# PSU3.net
KiCad netlist of a schematic drawn in Altium Designer
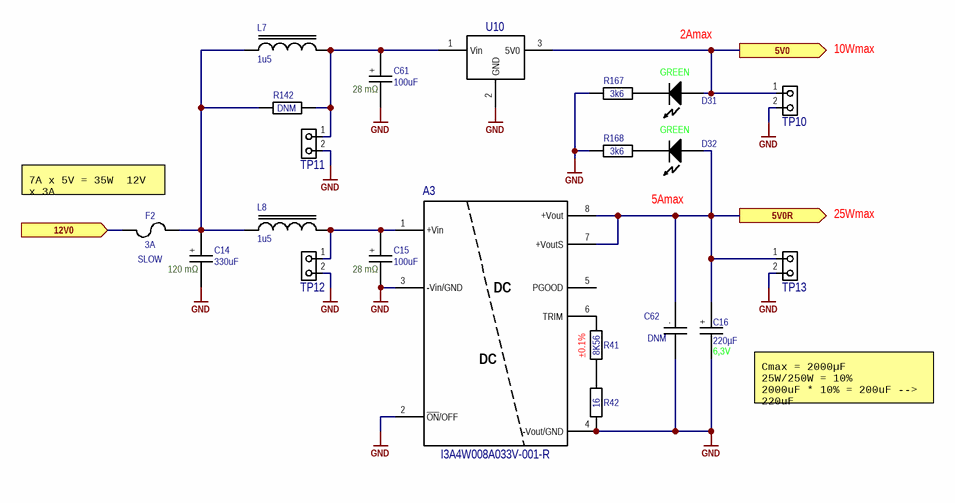
[diagram p0: PSU3.SchDoc]

(export (version "E")
  (design (tool "Eeschema 10.0.6"))
  (components
    (comp (ref "A3")
      (value "A")
      (footprint "I3A-POSETIVE")
      (description "DC DC CONVERTER 3.3-16.5V")
      (fields
        (field (name "02. DISTRIBUTOR PART NUMBER") "285-2720-ND")
        (field (name "07. MANUFACTURER  PART NUMBER") "I3A4W008A033V-001-R")
        (field (name "NICNAME") "I3A4W008A033V-001-R")
        (field (name "13. CREATED DATE/NAME") "AUG 2018 / Hören")
      )
      (libsource (lib "tom") (part "i3A4W008A033V-001-R"))
    )
    (comp (ref "C14")
      (value "330uF")
      (footprint "SMD-CAP-ALU-G")
      (description "CAP ALUM 330UF 20% 50V SMD")
      (fields
        (field (name "TOLERANCE") "±20%")
        (field (name "ESR") "120 mΩ")
        (field (name "02. DISTRIBUTOR PART NUMBER") "PCE5026DKR-ND")
        (field (name "13. CREATED DATE/NAME") "AUG2018/Hören")
      )
      (libsource (lib "chickenfood") (part "C+"))
    )
    (comp (ref "C15")
      (value "100uF")
      (footprint "SMD-CAP-ALU-G")
      (description "CAP ALUM POLY HYB 100UF 50V SMD")
      (fields
        (field (name "TOLERANCE") "±20%")
        (field (name "ESR") "28 mΩ")
        (field (name "02. DISTRIBUTOR PART NUMBER") "P15442DKR-ND")
        (field (name "13. CREATED DATE/NAME") "AUG2018/Hören")
      )
      (libsource (lib "chickenfood") (part "C+"))
    )
    (comp (ref "C16")
      (value "220µF")
      (footprint "SMD-CAP-ALU-E")
      (description "CAP ALUM 220UF 20% 6.3V SMD")
      (fields
        (field (name "TOLERANCE") "±20%")
        (field (name "VOLTAGE RATING") "6,3V")
        (field (name "02. DISTRIBUTOR PART NUMBER") "PCE3985DKR-ND")
        (field (name "13. CREATED DATE/NAME") "AUG2018/Hören")
      )
      (libsource (lib "chickenfood") (part "C+"))
    )
    (comp (ref "C61")
      (value "100uF")
      (footprint "SMD-CAP-ALU-G")
      (description "CAP ALUM POLY HYB 100UF 50V SMD")
      (fields
        (field (name "TOLERANCE") "±20%")
        (field (name "ESR") "28 mΩ")
        (field (name "02. DISTRIBUTOR PART NUMBER") "P15442DKR-ND")
        (field (name "13. CREATED DATE/NAME") "AUG2018/Hören")
      )
      (libsource (lib "chickenfood") (part "C+"))
    )
    (comp (ref "C62")
      (value "DNM")
      (footprint "C0402 Reflow")
      (description "CAP CER 0.1UF 16V X7R 0402")
      (fields
        (field (name "TOLERANCE") "±5%")
        (field (name "02. DISTRIBUTOR PART NUMBER") "399-7761-6-ND")
        (field (name "13. CREATED DATE/NAME") "AUG2018/Hören")
      )
      (libsource (lib "chickenfood") (part "C"))
    )
    (comp (ref "D31")
      (value "D")
      (footprint "L0603G")
      (description "LED GREEN DIFFUSED 0603 SMD")
      (fields
        (field (name "02. DISTRIBUTOR PART NUMBER") "475-2709-6-ND")
        (field (name "07. MANUFACTURER  PART NUMBER") "LG L29K-G2J1-24-Z")
        (field (name "COLOR") "GREEN")
        (field (name "13. CREATED DATE/NAME") "AUG2018/Hören")
      )
      (libsource (lib "chickenfood") (part "LED"))
    )
    (comp (ref "D32")
      (value "D")
      (footprint "L0603G")
      (description "LED GREEN DIFFUSED 0603 SMD")
      (fields
        (field (name "02. DISTRIBUTOR PART NUMBER") "475-2709-6-ND")
        (field (name "07. MANUFACTURER  PART NUMBER") "LG L29K-G2J1-24-Z")
        (field (name "COLOR") "GREEN")
        (field (name "13. CREATED DATE/NAME") "AUG2018/Hören")
      )
      (libsource (lib "chickenfood") (part "LED"))
    )
    (comp (ref "F2")
      (value "3A")
      (footprint "OMNI-Fuse")
      (description "FUSE BOARD MNT 3A 125VAC/VDC SMD")
      (fields
        (field (name "02. DISTRIBUTOR PART NUMBER") "F10747DKR-ND")
        (field (name "07. MANUFACTURER  PART NUMBER") "0154003.DRTL")
        (field (name "SPEED") "SLOW")
        (field (name "13. CREATED DATE/NAME") "AUG 2018 / Hören")
      )
      (libsource (lib "tom") (part "Fuse"))
    )
    (comp (ref "L7")
      (value "L")
      (footprint "XAL4020")
      (description "Fixed Inductors 1.5uH Shld 20% 7.5A 23.6mOhms AECQ2")
      (fields
        (field (name "02. DISTRIBUTOR PART NUMBER") "994-XAL4020-152MEC")
        (field (name "07. MANUFACTURER  PART NUMBER") "XAL4020-152MEC")
        (field (name "INDUCTANCE") "1u5")
      )
      (libsource (lib "PCB-Tester-Board-V1") (part "INDUCTOR"))
    )
    (comp (ref "L8")
      (value "L")
      (footprint "XAL4020")
      (description "Fixed Inductors 1.5uH Shld 20% 7.5A 23.6mOhms AECQ2")
      (fields
        (field (name "02. DISTRIBUTOR PART NUMBER") "994-XAL4020-152MEC")
        (field (name "07. MANUFACTURER  PART NUMBER") "XAL4020-152MEC")
        (field (name "INDUCTANCE") "1u5")
      )
      (libsource (lib "PCB-Tester-Board-V1") (part "INDUCTOR"))
    )
    (comp (ref "R41")
      (value "8K56")
      (footprint "R0603 Reflow")
      (description "RES 8.56K OHM 0.1% 1/8W 0603")
      (fields
        (field (name "TOLERANCE") "±0.1%")
        (field (name "02. DISTRIBUTOR PART NUMBER") "541-4554-6-ND")
        (field (name "07. MANUFACTURER  PART NUMBER") "TNPW06038K56BEEA")
        (field (name "13. CREATED DATE/NAME") "AUG2018/Hören")
      )
      (libsource (lib "chickenfood") (part "R"))
    )
    (comp (ref "R42")
      (value "16")
      (footprint "R0603 Reflow")
      (description "RES SMD 16 OHM 1% 1/10W 0603")
      (fields
        (field (name "TOLERANCE") "±1%")
        (field (name "02. DISTRIBUTOR PART NUMBER") "311-16.0HRDKR-ND")
        (field (name "13. CREATED DATE/NAME") "AUG2018/Hören")
      )
      (libsource (lib "chickenfood") (part "R"))
    )
    (comp (ref "R142")
      (value "DNM")
      (footprint "R1206 Reflow")
      (description "RES SMD 0 OHM JUMPER 1206")
      (fields (field (name "Comment") "R"))
      (libsource (lib "PCB-Tester-Board-V1") (part "R_25"))
    )
    (comp (ref "R167")
      (value "3k6")
      (footprint "R0603 Reflow")
      (description "RES SMD 3.6K OHM 1% 1/10W 0603")
      (fields
        (field (name "TOLERANCE") "±1%")
        (field (name "02. DISTRIBUTOR PART NUMBER") "311-3.60KHRCT-ND")
        (field (name "13. CREATED DATE/NAME") "AUG2018/Hören")
      )
      (libsource (lib "") (part "R_1"))
    )
    (comp (ref "R168")
      (value "3k6")
      (footprint "R0603 Reflow")
      (description "RES SMD 3.6K OHM 1% 1/10W 0603")
      (fields
        (field (name "TOLERANCE") "±1%")
        (field (name "02. DISTRIBUTOR PART NUMBER") "311-3.60KHRCT-ND")
        (field (name "13. CREATED DATE/NAME") "AUG2018/Hören")
      )
      (libsource (lib "") (part "R_1"))
    )
    (comp (ref "TP10")
      (value "TP")
      (footprint "DualTestpoint 100mils")
      (description "Dual testpoint, pitch 2.54mm")
      (fields
        (field (name "02. DISTRIBUTOR PART NUMBER") "HMTSW-103-07-G-S-240")
        (field (name "13. CREATED DATE/NAME") "AUG2018/Hören")
      )
      (libsource (lib "PCB-Tester-Board-V1") (part "DualTestpoint 100mils"))
    )
    (comp (ref "TP11")
      (value "TP")
      (footprint "DualTestpoint 100mils")
      (description "Dual testpoint, pitch 2.54mm")
      (fields
        (field (name "02. DISTRIBUTOR PART NUMBER") "HMTSW-103-07-G-S-240")
        (field (name "13. CREATED DATE/NAME") "AUG2018/Hören")
      )
      (libsource (lib "PCB-Tester-Board-V1") (part "DualTestpoint 100mils"))
    )
    (comp (ref "TP12")
      (value "TP")
      (footprint "DualTestpoint 100mils")
      (description "Dual testpoint, pitch 2.54mm")
      (fields
        (field (name "02. DISTRIBUTOR PART NUMBER") "HMTSW-103-07-G-S-240")
        (field (name "13. CREATED DATE/NAME") "AUG2018/Hören")
      )
      (libsource (lib "PCB-Tester-Board-V1") (part "DualTestpoint 100mils"))
    )
    (comp (ref "TP13")
      (value "TP")
      (footprint "DualTestpoint 100mils")
      (description "Dual testpoint, pitch 2.54mm")
      (fields
        (field (name "02. DISTRIBUTOR PART NUMBER") "HMTSW-103-07-G-S-240")
        (field (name "13. CREATED DATE/NAME") "AUG2018/Hören")
      )
      (libsource (lib "PCB-Tester-Board-V1") (part "DualTestpoint 100mils"))
    )
    (comp (ref "U10")
      (value "U")
      (footprint "3SIP Traco")
      (description "DC DC CONVERTER 5V 10W")
      (fields
        (field (name "02. DISTRIBUTOR PART NUMBER") "1951-2692-ND")
        (field (name "07. MANUFACTURER  PART NUMBER") "TSR 2-2450")
        (field (name "13. CREATED DATE/NAME") "AUG 2018 / Hören")
      )
      (libsource (lib "tom") (part "TSR 2-2450"))
    )
  )
  (nets
    (net (code "1") (name "/5V0") (class "Default")
      (node (ref "D31") (pin "1") (pinfunction "Anode_1") (pintype "passive"))
      (node (ref "TP10") (pin "1") (pinfunction "1_1") (pintype "passive"))
      (node (ref "U10") (pin "3") (pinfunction "5V0_3") (pintype "passive"))
    )
    (net (code "2") (name "/5V0R") (class "Default")
      (node (ref "A3") (pin "7") (pinfunction "+VoutS_7") (pintype "passive"))
      (node (ref "A3") (pin "8") (pinfunction "+Vout_8") (pintype "passive"))
      (node (ref "C16") (pin "1") (pinfunction "1_1") (pintype "passive"))
      (node (ref "C62") (pin "1") (pinfunction "1_1") (pintype "passive"))
      (node (ref "D32") (pin "1") (pinfunction "Anode_1") (pintype "passive"))
      (node (ref "TP13") (pin "1") (pinfunction "1_1") (pintype "passive"))
    )
    (net (code "3") (name "/12V0") (class "Default")
      (node (ref "F2") (pin "1") (pinfunction "1_1") (pintype "passive"))
    )
    (net (code "4") (name "GND") (class "Default")
      (node (ref "A3") (pin "2") (pinfunction "~{ON}/OFF_2") (pintype "passive"))
      (node (ref "A3") (pin "3") (pinfunction "-Vin/GND_3") (pintype "passive"))
      (node (ref "A3") (pin "4") (pinfunction "-Vout/GND_4") (pintype "passive"))
      (node (ref "C14") (pin "2") (pinfunction "2_2") (pintype "passive"))
      (node (ref "C15") (pin "2") (pinfunction "2_2") (pintype "passive"))
      (node (ref "C16") (pin "2") (pinfunction "2_2") (pintype "passive"))
      (node (ref "C61") (pin "2") (pinfunction "2_2") (pintype "passive"))
      (node (ref "C62") (pin "2") (pinfunction "2_2") (pintype "passive"))
      (node (ref "R167") (pin "1") (pinfunction "1_1") (pintype "passive"))
      (node (ref "R168") (pin "1") (pinfunction "1_1") (pintype "passive"))
      (node (ref "R42") (pin "1") (pinfunction "1_1") (pintype "passive"))
      (node (ref "TP10") (pin "2") (pinfunction "2_2") (pintype "passive"))
      (node (ref "TP11") (pin "2") (pinfunction "2_2") (pintype "passive"))
      (node (ref "TP12") (pin "2") (pinfunction "2_2") (pintype "passive"))
      (node (ref "TP13") (pin "2") (pinfunction "2_2") (pintype "passive"))
      (node (ref "U10") (pin "2") (pinfunction "GND_2") (pintype "passive"))
    )
    (net (code "5") (name "Net-(A3-+Vin)") (class "Default")
      (node (ref "A3") (pin "1") (pinfunction "+Vin_1") (pintype "passive"))
      (node (ref "C15") (pin "1") (pinfunction "1_1") (pintype "passive"))
      (node (ref "L8") (pin "1") (pinfunction "1_1") (pintype "passive"))
      (node (ref "TP12") (pin "1") (pinfunction "1_1") (pintype "passive"))
    )
    (net (code "6") (name "Net-(A3-TRIM)") (class "Default")
      (node (ref "A3") (pin "6") (pinfunction "TRIM_6") (pintype "passive"))
      (node (ref "R41") (pin "2") (pinfunction "2_2") (pintype "passive"))
    )
    (net (code "7") (name "Net-(C14-Pad1)") (class "Default")
      (node (ref "C14") (pin "1") (pinfunction "1_1") (pintype "passive"))
      (node (ref "F2") (pin "2") (pinfunction "2_2") (pintype "passive"))
      (node (ref "L7") (pin "2") (pinfunction "2_2") (pintype "passive"))
      (node (ref "L8") (pin "2") (pinfunction "2_2") (pintype "passive"))
      (node (ref "R142") (pin "1") (pinfunction "1_1") (pintype "passive"))
    )
    (net (code "8") (name "Net-(D31-Cathode)") (class "Default")
      (node (ref "D31") (pin "2") (pinfunction "Cathode_2") (pintype "passive"))
      (node (ref "R167") (pin "2") (pinfunction "2_2") (pintype "passive"))
    )
    (net (code "9") (name "Net-(D32-Cathode)") (class "Default")
      (node (ref "D32") (pin "2") (pinfunction "Cathode_2") (pintype "passive"))
      (node (ref "R168") (pin "2") (pinfunction "2_2") (pintype "passive"))
    )
    (net (code "10") (name "Net-(R41-Pad1)") (class "Default")
      (node (ref "R41") (pin "1") (pinfunction "1_1") (pintype "passive"))
      (node (ref "R42") (pin "2") (pinfunction "2_2") (pintype "passive"))
    )
    (net (code "11") (name "Net-(U10-Vin)") (class "Default")
      (node (ref "C61") (pin "1") (pinfunction "1_1") (pintype "passive"))
      (node (ref "L7") (pin "1") (pinfunction "1_1") (pintype "passive"))
      (node (ref "R142") (pin "2") (pinfunction "2_2") (pintype "passive"))
      (node (ref "TP11") (pin "1") (pinfunction "1_1") (pintype "passive"))
      (node (ref "U10") (pin "1") (pinfunction "Vin_1") (pintype "passive"))
    )
    (net (code "12") (name "unconnected-(A3-PGOOD-Pad5)") (class "Default")
      (node (ref "A3") (pin "5") (pinfunction "PGOOD_5") (pintype "passive"))
    )
  )
)
